# Duinopeak-Mazebot-v0_1.net
KiCad netlist of a schematic drawn in EAGLE
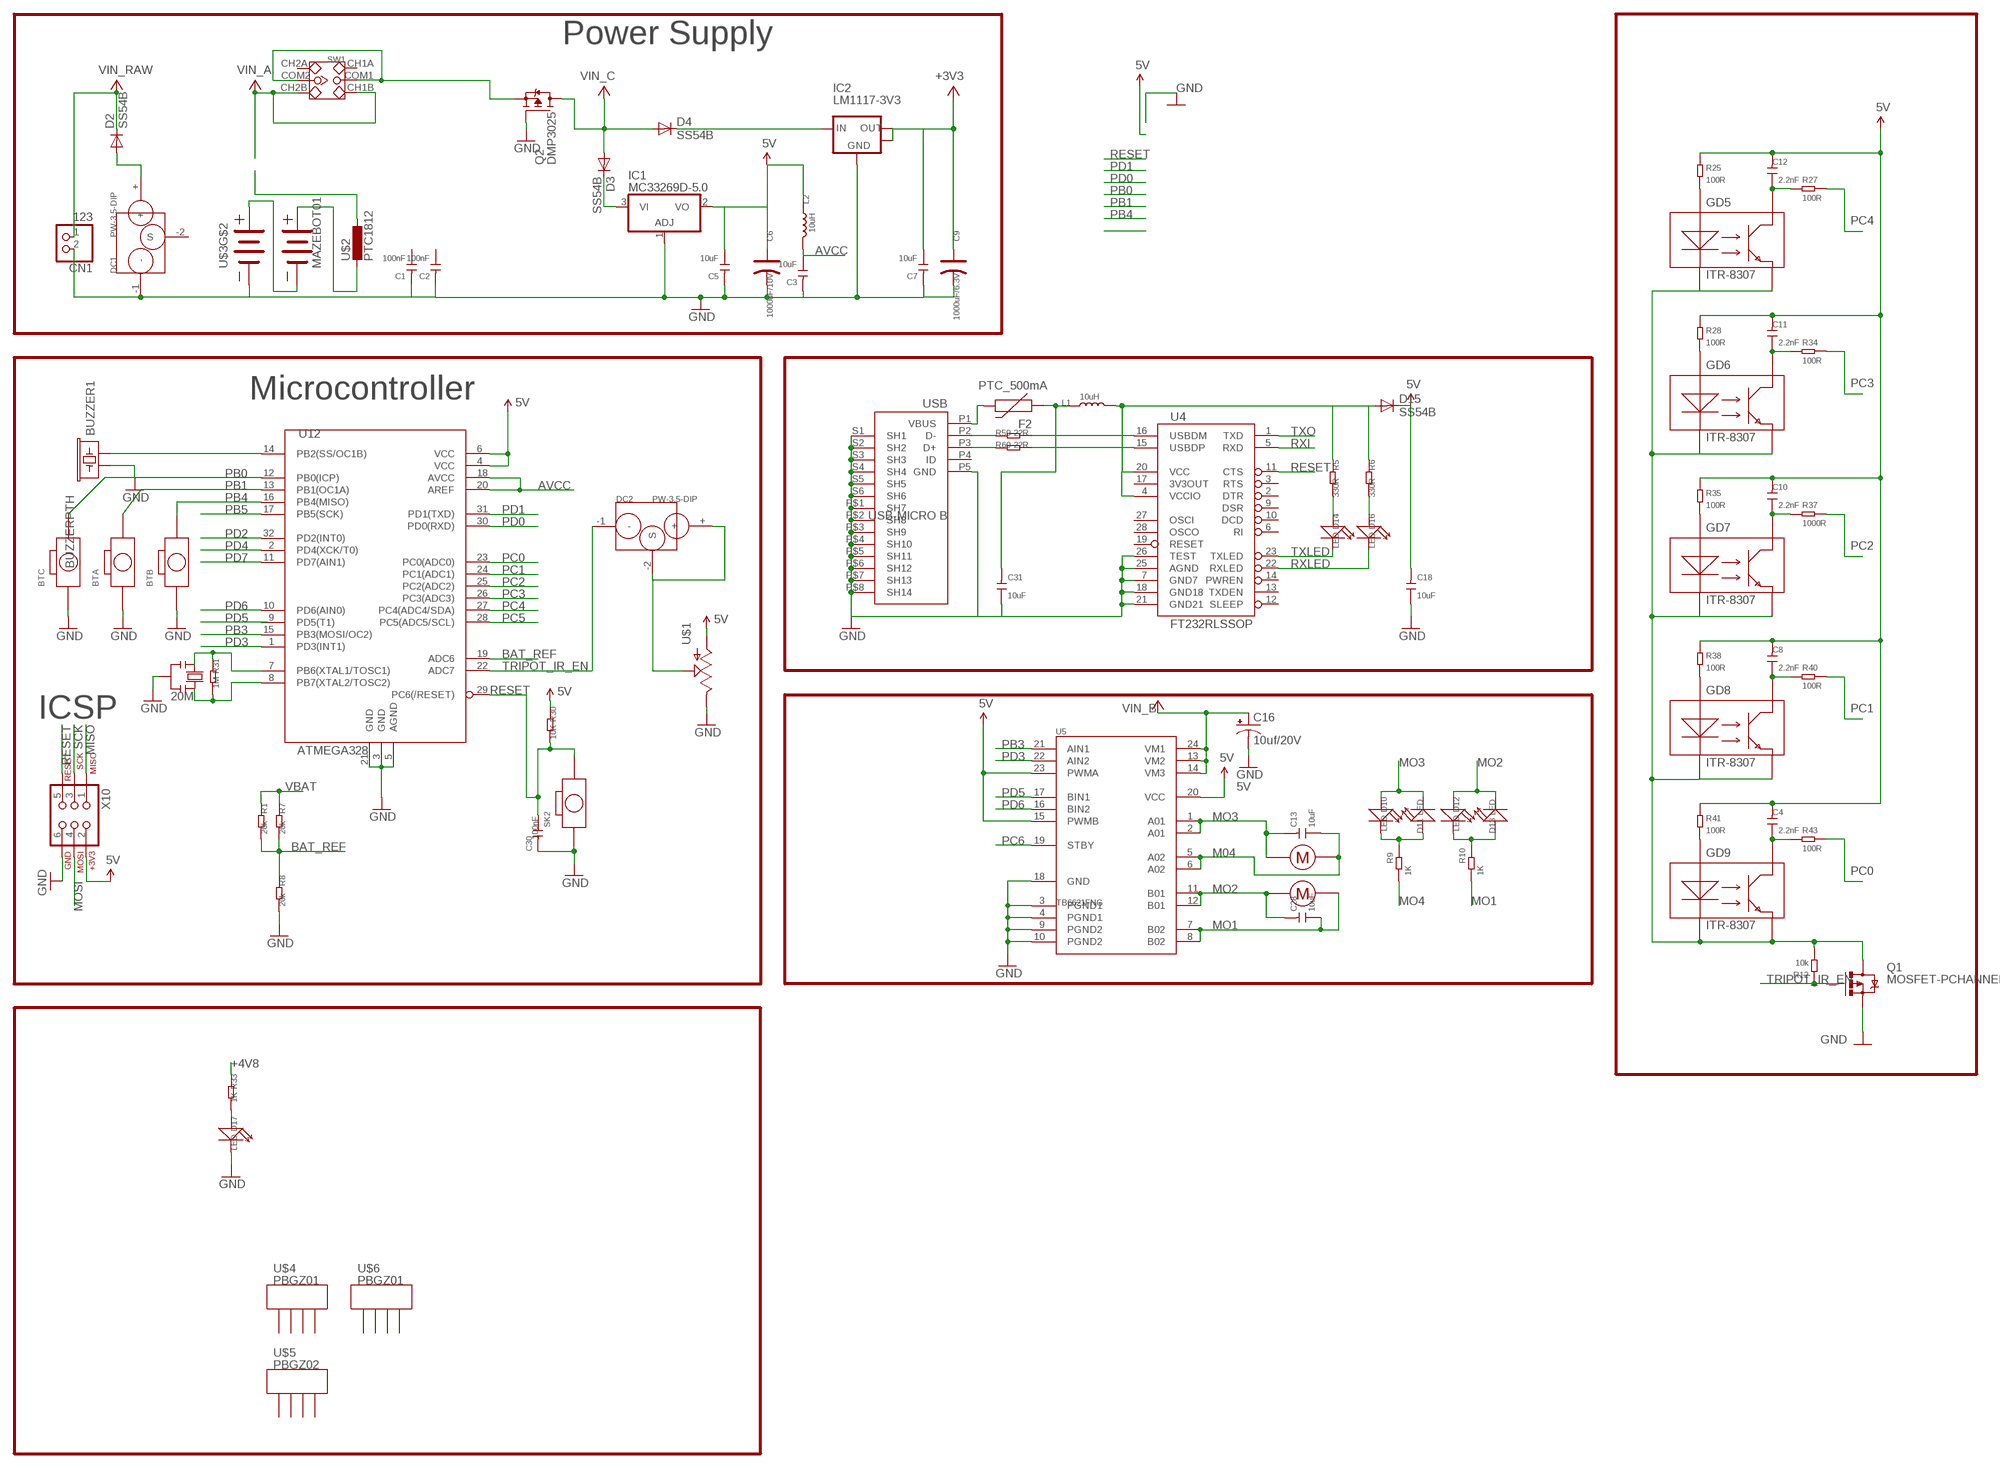
[diagram p0: schematic, sheet 1]

(export (version "E")
  (design (tool "Eeschema 10.0.6"))
  (components
    (comp (ref "BTA")
      (value "BOTTON-2P-90")
      (footprint "eagle-import:2P-7.62X3.56-90D")
      (libsource (lib "eagle-import") (part "BOTTON-2P-90"))
    )
    (comp (ref "BTB")
      (value "BOTTON-2P-90")
      (footprint "eagle-import:2P-7.62X3.56-90D")
      (libsource (lib "eagle-import") (part "BOTTON-2P-90"))
    )
    (comp (ref "BTC")
      (value "BOTTON-2P-90")
      (footprint "eagle-import:2P-7.62X3.56-90D")
      (libsource (lib "eagle-import") (part "BOTTON-2P-90"))
    )
    (comp (ref "BUZZER1")
      (value "BUZZERPTH")
      (footprint "eagle-import:BUZZER-12MM")
      (libsource (lib "eagle-import") (part "BUZZERPTH"))
    )
    (comp (ref "C1")
      (value "100nF")
      (footprint "eagle-import:C0603")
      (libsource (lib "eagle-import") (part "C-0603"))
    )
    (comp (ref "C2")
      (value "100nF")
      (footprint "eagle-import:C0603")
      (libsource (lib "eagle-import") (part "C-0603"))
    )
    (comp (ref "C3")
      (value "10uF")
      (footprint "eagle-import:C0805")
      (libsource (lib "eagle-import") (part "C-0805"))
    )
    (comp (ref "C4")
      (value "2.2nF")
      (footprint "eagle-import:C0603")
      (libsource (lib "eagle-import") (part "C-0603"))
    )
    (comp (ref "C5")
      (value "10uF")
      (footprint "eagle-import:C0805")
      (libsource (lib "eagle-import") (part "C-0805"))
    )
    (comp (ref "C6")
      (value "1000uF/10V")
      (footprint "eagle-import:ELECTRO-8.2MM")
      (libsource (lib "eagle-import") (part "CAP-D8.2/3.05"))
    )
    (comp (ref "C7")
      (value "10uF")
      (footprint "eagle-import:C0805")
      (libsource (lib "eagle-import") (part "C-0805"))
    )
    (comp (ref "C8")
      (value "2.2nF")
      (footprint "eagle-import:C0603")
      (libsource (lib "eagle-import") (part "C-0603"))
    )
    (comp (ref "C9")
      (value "1000uF/6.3V")
      (footprint "eagle-import:ELECTRO-8.2MM")
      (libsource (lib "eagle-import") (part "CAP-D8.2/3.05"))
    )
    (comp (ref "C10")
      (value "2.2nF")
      (footprint "eagle-import:C0603")
      (libsource (lib "eagle-import") (part "C-0603"))
    )
    (comp (ref "C11")
      (value "2.2nF")
      (footprint "eagle-import:C0603")
      (libsource (lib "eagle-import") (part "C-0603"))
    )
    (comp (ref "C12")
      (value "2.2nF")
      (footprint "eagle-import:C0603")
      (libsource (lib "eagle-import") (part "C-0603"))
    )
    (comp (ref "C13")
      (value "10uF")
      (footprint "eagle-import:C0805")
      (libsource (lib "eagle-import") (part "C-0805"))
    )
    (comp (ref "C16")
      (value "10uf/20V")
      (footprint "eagle-import:EIA3216")
      (libsource (lib "eagle-import") (part "CAP_POL1206"))
    )
    (comp (ref "C18")
      (value "10uF")
      (footprint "eagle-import:C0603")
      (libsource (lib "eagle-import") (part "C-0603"))
    )
    (comp (ref "C28")
      (value "10uF")
      (footprint "eagle-import:C0805")
      (libsource (lib "eagle-import") (part "C-0805"))
    )
    (comp (ref "C30")
      (value "100nF")
      (footprint "eagle-import:C0603")
      (libsource (lib "eagle-import") (part "C-0603"))
    )
    (comp (ref "C31")
      (value "10uF")
      (footprint "eagle-import:C0805")
      (libsource (lib "eagle-import") (part "C-0805"))
    )
    (comp (ref "CN1")
      (value "123")
      (footprint "eagle-import:JST-PH-2-SMT-RA")
      (libsource (lib "eagle-import") (part "JST_2PIN-SMT-RA"))
    )
    (comp (ref "D2")
      (value "SS54B")
      (footprint "eagle-import:SMB")
      (libsource (lib "eagle-import") (part "DIODE-SMB"))
    )
    (comp (ref "D3")
      (value "SS54B")
      (footprint "eagle-import:SMB")
      (libsource (lib "eagle-import") (part "DIODE-SMB"))
    )
    (comp (ref "D4")
      (value "SS54B")
      (footprint "eagle-import:SMB")
      (libsource (lib "eagle-import") (part "DIODE-SMB"))
    )
    (comp (ref "D10")
      (value "LED")
      (footprint "eagle-import:LED-0603")
      (libsource (lib "eagle-import") (part "LED'0603'"))
    )
    (comp (ref "D11")
      (value "LED")
      (footprint "eagle-import:LED-0603")
      (libsource (lib "eagle-import") (part "LED'0603'"))
    )
    (comp (ref "D12")
      (value "LED")
      (footprint "eagle-import:LED-0603")
      (libsource (lib "eagle-import") (part "LED'0603'"))
    )
    (comp (ref "D13")
      (value "LED")
      (footprint "eagle-import:LED-0603")
      (libsource (lib "eagle-import") (part "LED'0603'"))
    )
    (comp (ref "D14")
      (value "LED")
      (footprint "eagle-import:LED-0603")
      (libsource (lib "eagle-import") (part "LED'0603'"))
    )
    (comp (ref "D15")
      (value "SS54B")
      (footprint "eagle-import:SMB")
      (libsource (lib "eagle-import") (part "DIODE-SMB"))
    )
    (comp (ref "D16")
      (value "LED")
      (footprint "eagle-import:LED-0603")
      (libsource (lib "eagle-import") (part "LED'0603'"))
    )
    (comp (ref "D17")
      (value "LED")
      (footprint "eagle-import:LED-0603")
      (libsource (lib "eagle-import") (part "LED'0603'"))
    )
    (comp (ref "DC1")
      (value "PW-3.5-DIP")
      (footprint "eagle-import:PW-3.5-DIP")
      (libsource (lib "eagle-import") (part "PW-3.5-DIP"))
    )
    (comp (ref "DC2")
      (value "PW-3.5-DIP")
      (footprint "eagle-import:PW-3.5-DIP")
      (libsource (lib "eagle-import") (part "PW-3.5-DIP"))
    )
    (comp (ref "F2")
      (value "PTC_500mA")
      (footprint "eagle-import:PTC-1206")
      (libsource (lib "eagle-import") (part "PTCSMD"))
    )
    (comp (ref "GD5")
      (value "ITR-8307")
      (footprint "eagle-import:ITR-8307")
      (libsource (lib "eagle-import") (part "ITR-8307"))
    )
    (comp (ref "GD6")
      (value "ITR-8307")
      (footprint "eagle-import:ITR-8307")
      (libsource (lib "eagle-import") (part "ITR-8307"))
    )
    (comp (ref "GD7")
      (value "ITR-8307")
      (footprint "eagle-import:ITR-8307")
      (libsource (lib "eagle-import") (part "ITR-8307"))
    )
    (comp (ref "GD8")
      (value "ITR-8307")
      (footprint "eagle-import:ITR-8307")
      (libsource (lib "eagle-import") (part "ITR-8307"))
    )
    (comp (ref "GD9")
      (value "ITR-8307")
      (footprint "eagle-import:ITR-8307")
      (libsource (lib "eagle-import") (part "ITR-8307"))
    )
    (comp (ref "IC1")
      (value "MC33269D-5.0")
      (footprint "eagle-import:DPACK")
      (libsource (lib "eagle-import") (part "MC33269?D"))
    )
    (comp (ref "IC2")
      (value "LM1117-3V3")
      (footprint "eagle-import:SOT223")
      (libsource (lib "eagle-import") (part "LM1117-SOT223"))
    )
    (comp (ref "L1")
      (value "10uH")
      (footprint "eagle-import:L0805")
      (libsource (lib "eagle-import") (part "L'0805'"))
    )
    (comp (ref "L2")
      (value "10uH")
      (footprint "eagle-import:L0805")
      (libsource (lib "eagle-import") (part "L'0805'"))
    )
    (comp (ref "Q1")
      (value "MOSFET-PCHANNEL")
      (footprint "eagle-import:SOT23")
      (libsource (lib "eagle-import") (part "MOSFET-PCHANNEL"))
    )
    (comp (ref "Q2")
      (value "DMP3025")
      (footprint "eagle-import:TO252")
      (libsource (lib "eagle-import") (part "SPD30P06PTO252"))
    )
    (comp (ref "R1")
      (value "20k")
      (footprint "eagle-import:R0603")
      (libsource (lib "eagle-import") (part "R-0603"))
    )
    (comp (ref "R5")
      (value "330R")
      (footprint "eagle-import:R0603")
      (libsource (lib "eagle-import") (part "R-0603"))
    )
    (comp (ref "R6")
      (value "330R")
      (footprint "eagle-import:R0603")
      (libsource (lib "eagle-import") (part "R-0603"))
    )
    (comp (ref "R7")
      (value "20k")
      (footprint "eagle-import:R0603")
      (libsource (lib "eagle-import") (part "R-0603"))
    )
    (comp (ref "R8")
      (value "20k")
      (footprint "eagle-import:R0603")
      (libsource (lib "eagle-import") (part "R-0603"))
    )
    (comp (ref "R9")
      (value "1K")
      (footprint "eagle-import:R0603")
      (libsource (lib "eagle-import") (part "R-0603"))
    )
    (comp (ref "R10")
      (value "1K")
      (footprint "eagle-import:R0603")
      (libsource (lib "eagle-import") (part "R-0603"))
    )
    (comp (ref "R12")
      (value "10k")
      (footprint "eagle-import:R0603")
      (libsource (lib "eagle-import") (part "R-0603"))
    )
    (comp (ref "R25")
      (value "100R")
      (footprint "eagle-import:R0603")
      (libsource (lib "eagle-import") (part "R-0603"))
    )
    (comp (ref "R27")
      (value "100R")
      (footprint "eagle-import:R0603")
      (libsource (lib "eagle-import") (part "R-0603"))
    )
    (comp (ref "R28")
      (value "100R")
      (footprint "eagle-import:R0603")
      (libsource (lib "eagle-import") (part "R-0603"))
    )
    (comp (ref "R30")
      (value "10K")
      (footprint "eagle-import:R0603")
      (libsource (lib "eagle-import") (part "R-0603"))
    )
    (comp (ref "R31")
      (value "1M")
      (footprint "eagle-import:R0603")
      (libsource (lib "eagle-import") (part "R-0603"))
    )
    (comp (ref "R33")
      (value "1K")
      (footprint "eagle-import:R0603")
      (libsource (lib "eagle-import") (part "R-0603"))
    )
    (comp (ref "R34")
      (value "100R")
      (footprint "eagle-import:R0603")
      (libsource (lib "eagle-import") (part "R-0603"))
    )
    (comp (ref "R35")
      (value "100R")
      (footprint "eagle-import:R0603")
      (libsource (lib "eagle-import") (part "R-0603"))
    )
    (comp (ref "R37")
      (value "1000R")
      (footprint "eagle-import:R0603")
      (libsource (lib "eagle-import") (part "R-0603"))
    )
    (comp (ref "R38")
      (value "100R")
      (footprint "eagle-import:R0603")
      (libsource (lib "eagle-import") (part "R-0603"))
    )
    (comp (ref "R40")
      (value "100R")
      (footprint "eagle-import:R0603")
      (libsource (lib "eagle-import") (part "R-0603"))
    )
    (comp (ref "R41")
      (value "100R")
      (footprint "eagle-import:R0603")
      (libsource (lib "eagle-import") (part "R-0603"))
    )
    (comp (ref "R43")
      (value "100R")
      (footprint "eagle-import:R0603")
      (libsource (lib "eagle-import") (part "R-0603"))
    )
    (comp (ref "R59")
      (value "22R")
      (footprint "eagle-import:R0603")
      (libsource (lib "eagle-import") (part "R-0603"))
    )
    (comp (ref "R60")
      (value "22R")
      (footprint "eagle-import:R0603")
      (libsource (lib "eagle-import") (part "R-0603"))
    )
    (comp (ref "SK2")
      (value "BOTTON-2P-90")
      (footprint "eagle-import:2P-7.62X3.56-90D")
      (libsource (lib "eagle-import") (part "BOTTON-2P-90"))
    )
    (comp (ref "SW1")
      (value "SWITCH-2CH-6P'90D'")
      (footprint "eagle-import:6P-2CH-2.54-9.0X3.6-90D")
      (libsource (lib "eagle-import") (part "SWITCH-2CH-6P'90D'"))
    )
    (comp (ref "U$1")
      (value "POTTRIM")
      (footprint "eagle-import:TRIM_POT")
      (libsource (lib "eagle-import") (part "POTTRIM"))
    )
    (comp (ref "U$2")
      (value "PTC1812")
      (footprint "eagle-import:PTC-L1812")
      (libsource (lib "eagle-import") (part "PTC1812"))
    )
    (comp (ref "U$3")
      (value "MAZEBOT01")
      (footprint "eagle-import:MAZEBOT-P1")
      (libsource (lib "eagle-import") (part "MAZEBOT01"))
    )
    (comp (ref "U$4")
      (value "PBGZ01")
      (footprint "eagle-import:PBGZ-22X33MM")
      (libsource (lib "eagle-import") (part "PBGZ01"))
    )
    (comp (ref "U$5")
      (value "PBGZ02")
      (footprint "eagle-import:PBGZ-20X55MM")
      (libsource (lib "eagle-import") (part "PBGZ02"))
    )
    (comp (ref "U$6")
      (value "PBGZ01")
      (footprint "eagle-import:PBGZ-22X33MM")
      (libsource (lib "eagle-import") (part "PBGZ01"))
    )
    (comp (ref "U4")
      (value "FT232RLSSOP")
      (footprint "eagle-import:SSOP28DB")
      (libsource (lib "eagle-import") (part "FT232RLSSOP"))
    )
    (comp (ref "U5")
      (value "TB6621FNG")
      (footprint "eagle-import:SSOP24")
      (libsource (lib "eagle-import") (part "TB6621FNG"))
    )
    (comp (ref "U12")
      (value "ATMEGA328")
      (footprint "eagle-import:TQFP32-08")
      (libsource (lib "eagle-import") (part "ATMEGA168"))
    )
    (comp (ref "USB")
      (value "USB-MICRO B")
      (footprint "eagle-import:CON2_USB_MICRO_B_AT")
      (libsource (lib "eagle-import") (part "MYCON2_USB-MINI-B"))
    )
    (comp (ref "X10")
      (value "AVR_SPI_PRG_62X3_LOCK")
      (footprint "eagle-import:2X3_LOCK")
      (libsource (lib "eagle-import") (part "AVR_SPI_PRG_62X3_LOCK"))
    )
    (comp (ref "Y1")
      (value "20M")
      (footprint "eagle-import:RESONATOR")
      (libsource (lib "eagle-import") (part "RESONATORMU"))
    )
  )
  (nets
    (net (code "1") (name "+3V3") (class "Default")
      (node (ref "C7") (pin "1") (pinfunction "1_1") (pintype "passive"))
      (node (ref "C9") (pin "1") (pinfunction "+_1") (pintype "passive"))
      (node (ref "IC2") (pin "2") (pinfunction "OUT_2") (pintype "output"))
      (node (ref "IC2") (pin "4") (pinfunction "OUT_4") (pintype "output"))
    )
    (net (code "2") (name "+4V8") (class "Default")
      (node (ref "R33") (pin "1") (pinfunction "1_1") (pintype "passive"))
    )
    (net (code "3") (name "5V") (class "Default")
      (node (ref "C10") (pin "2") (pinfunction "2_2") (pintype "passive"))
      (node (ref "C11") (pin "2") (pinfunction "2_2") (pintype "passive"))
      (node (ref "C12") (pin "2") (pinfunction "2_2") (pintype "passive"))
      (node (ref "C18") (pin "2") (pinfunction "2_2") (pintype "passive"))
      (node (ref "C4") (pin "2") (pinfunction "2_2") (pintype "passive"))
      (node (ref "C5") (pin "1") (pinfunction "1_1") (pintype "passive"))
      (node (ref "C6") (pin "1") (pinfunction "+_1") (pintype "passive"))
      (node (ref "C8") (pin "2") (pinfunction "2_2") (pintype "passive"))
      (node (ref "D15") (pin "C") (pinfunction "C_C") (pintype "passive"))
      (node (ref "IC1") (pin "2") (pinfunction "VO_2") (pintype "passive"))
      (node (ref "L2") (pin "1") (pinfunction "1_1") (pintype "passive"))
      (node (ref "R25") (pin "1") (pinfunction "1_1") (pintype "passive"))
      (node (ref "R28") (pin "1") (pinfunction "1_1") (pintype "passive"))
      (node (ref "R30") (pin "1") (pinfunction "1_1") (pintype "passive"))
      (node (ref "R35") (pin "1") (pinfunction "1_1") (pintype "passive"))
      (node (ref "R38") (pin "1") (pinfunction "1_1") (pintype "passive"))
      (node (ref "R41") (pin "1") (pinfunction "1_1") (pintype "passive"))
      (node (ref "U$1") (pin "3") (pinfunction "A_3") (pintype "passive"))
      (node (ref "U12") (pin "4") (pinfunction "VCC_4") (pintype "bidirectional"))
      (node (ref "U12") (pin "6") (pinfunction "VCC_6") (pintype "bidirectional"))
      (node (ref "U5") (pin "15") (pinfunction "PWMB_15") (pintype "bidirectional"))
      (node (ref "U5") (pin "20") (pinfunction "VCC_20") (pintype "bidirectional"))
      (node (ref "U5") (pin "23") (pinfunction "PWMA_23") (pintype "bidirectional"))
      (node (ref "X10") (pin "2") (pinfunction "2_2") (pintype "passive"))
    )
    (net (code "4") (name "AVCC") (class "Default")
      (node (ref "C3") (pin "1") (pinfunction "1_1") (pintype "passive"))
      (node (ref "L2") (pin "2") (pinfunction "2_2") (pintype "passive"))
      (node (ref "U12") (pin "18") (pinfunction "AVCC_18") (pintype "bidirectional"))
      (node (ref "U12") (pin "20") (pinfunction "AREF_20") (pintype "bidirectional"))
    )
    (net (code "5") (name "BAT_REF") (class "Default")
      (node (ref "R1") (pin "2") (pinfunction "2_2") (pintype "passive"))
      (node (ref "R7") (pin "2") (pinfunction "2_2") (pintype "passive"))
      (node (ref "R8") (pin "1") (pinfunction "1_1") (pintype "passive"))
      (node (ref "U12") (pin "19") (pinfunction "ADC6_19") (pintype "bidirectional"))
    )
    (net (code "6") (name "GND") (class "Default")
      (node (ref "BTA") (pin "P$1") (pinfunction "1_P$1") (pintype "bidirectional"))
      (node (ref "BTB") (pin "P$1") (pinfunction "1_P$1") (pintype "bidirectional"))
      (node (ref "BTC") (pin "P$1") (pinfunction "1_P$1") (pintype "bidirectional"))
      (node (ref "BUZZER1") (pin "+") (pinfunction "1_+") (pintype "passive"))
      (node (ref "C1") (pin "2") (pinfunction "2_2") (pintype "passive"))
      (node (ref "C16") (pin "C") (pinfunction "-_C") (pintype "passive"))
      (node (ref "C18") (pin "1") (pinfunction "1_1") (pintype "passive"))
      (node (ref "C2") (pin "2") (pinfunction "2_2") (pintype "passive"))
      (node (ref "C3") (pin "2") (pinfunction "2_2") (pintype "passive"))
      (node (ref "C30") (pin "2") (pinfunction "2_2") (pintype "passive"))
      (node (ref "C31") (pin "1") (pinfunction "1_1") (pintype "passive"))
      (node (ref "C5") (pin "2") (pinfunction "2_2") (pintype "passive"))
      (node (ref "C6") (pin "2") (pinfunction "-_2") (pintype "passive"))
      (node (ref "C7") (pin "2") (pinfunction "2_2") (pintype "passive"))
      (node (ref "C9") (pin "2") (pinfunction "-_2") (pintype "passive"))
      (node (ref "CN1") (pin "2") (pinfunction "1_2") (pintype "passive"))
      (node (ref "D17") (pin "-") (pinfunction "-_-") (pintype "passive"))
      (node (ref "DC1") (pin "-1") (pinfunction "-_-1") (pintype "bidirectional"))
      (node (ref "IC1") (pin "1") (pinfunction "ADJ_1") (pintype "input"))
      (node (ref "IC2") (pin "1") (pinfunction "GND_1") (pintype "input"))
      (node (ref "Q1") (pin "2") (pinfunction "S_2") (pintype "passive"))
      (node (ref "Q2") (pin "1") (pinfunction "G_1") (pintype "passive"))
      (node (ref "R8") (pin "2") (pinfunction "2_2") (pintype "passive"))
      (node (ref "SK2") (pin "P$1") (pinfunction "1_P$1") (pintype "bidirectional"))
      (node (ref "U$1") (pin "2") (pinfunction "E_2") (pintype "passive"))
      (node (ref "U$3") (pin "D1") (pinfunction "D1_D1") (pintype "bidirectional"))
      (node (ref "U12") (pin "21") (pinfunction "GND_21") (pintype "bidirectional"))
      (node (ref "U12") (pin "3") (pinfunction "GND_3") (pintype "bidirectional"))
      (node (ref "U12") (pin "5") (pinfunction "AGND_5") (pintype "bidirectional"))
      (node (ref "U4") (pin "18") (pinfunction "GND18_18") (pintype "power_in"))
      (node (ref "U4") (pin "21") (pinfunction "GND21_21") (pintype "power_in"))
      (node (ref "U4") (pin "25") (pinfunction "AGND_25") (pintype "power_in"))
      (node (ref "U4") (pin "26") (pinfunction "TEST_26") (pintype "input"))
      (node (ref "U4") (pin "7") (pinfunction "GND7_7") (pintype "power_in"))
      (node (ref "U5") (pin "10") (pinfunction "PGND2_10") (pintype "bidirectional"))
      (node (ref "U5") (pin "18") (pinfunction "GND_18") (pintype "bidirectional"))
      (node (ref "U5") (pin "3") (pinfunction "PGND1_3") (pintype "bidirectional"))
      (node (ref "U5") (pin "4") (pinfunction "PGND1_4") (pintype "bidirectional"))
      (node (ref "U5") (pin "9") (pinfunction "PGND2_9") (pintype "bidirectional"))
      (node (ref "USB") (pin "P$1") (pinfunction "SH7_P$1") (pintype "passive"))
      (node (ref "USB") (pin "P$2") (pinfunction "SH8_P$2") (pintype "passive"))
      (node (ref "USB") (pin "P$3") (pinfunction "SH9_P$3") (pintype "passive"))
      (node (ref "USB") (pin "P$4") (pinfunction "SH10_P$4") (pintype "passive"))
      (node (ref "USB") (pin "P$5") (pinfunction "SH11_P$5") (pintype "passive"))
      (node (ref "USB") (pin "P$6") (pinfunction "SH12_P$6") (pintype "passive"))
      (node (ref "USB") (pin "P$7") (pinfunction "SH13_P$7") (pintype "passive"))
      (node (ref "USB") (pin "P$8") (pinfunction "SH14_P$8") (pintype "passive"))
      (node (ref "USB") (pin "P5") (pinfunction "GND_P5") (pintype "passive"))
      (node (ref "USB") (pin "S1") (pinfunction "SH1_S1") (pintype "passive"))
      (node (ref "USB") (pin "S2") (pinfunction "SH2_S2") (pintype "passive"))
      (node (ref "USB") (pin "S3") (pinfunction "SH3_S3") (pintype "passive"))
      (node (ref "USB") (pin "S4") (pinfunction "SH4_S4") (pintype "passive"))
      (node (ref "USB") (pin "S5") (pinfunction "SH5_S5") (pintype "passive"))
      (node (ref "USB") (pin "S6") (pinfunction "SH6_S6") (pintype "passive"))
      (node (ref "X10") (pin "6") (pinfunction "6_6") (pintype "passive"))
      (node (ref "Y1") (pin "2") (pinfunction "2_2") (pintype "passive"))
    )
    (net (code "7") (name "M04") (class "Default")
      (node (ref "C13") (pin "1") (pinfunction "1_1") (pintype "passive"))
      (node (ref "U$3") (pin "M2") (pinfunction "M2_M2") (pintype "bidirectional"))
      (node (ref "U5") (pin "5") (pinfunction "A02_5") (pintype "bidirectional"))
      (node (ref "U5") (pin "6") (pinfunction "A02_6") (pintype "bidirectional"))
    )
    (net (code "8") (name "MISO") (class "Default")
      (node (ref "X10") (pin "1") (pinfunction "1_1") (pintype "passive"))
    )
    (net (code "9") (name "MO1") (class "Default")
      (node (ref "C28") (pin "1") (pinfunction "1_1") (pintype "passive"))
      (node (ref "R10") (pin "2") (pinfunction "2_2") (pintype "passive"))
      (node (ref "U$3") (pin "M4") (pinfunction "M4_M4") (pintype "bidirectional"))
      (node (ref "U5") (pin "7") (pinfunction "B02_7") (pintype "bidirectional"))
      (node (ref "U5") (pin "8") (pinfunction "B02_8") (pintype "bidirectional"))
    )
    (net (code "10") (name "MO2") (class "Default")
      (node (ref "C28") (pin "2") (pinfunction "2_2") (pintype "passive"))
      (node (ref "D12") (pin "+") (pinfunction "+_+") (pintype "passive"))
      (node (ref "D13") (pin "-") (pinfunction "-_-") (pintype "passive"))
      (node (ref "U$3") (pin "M3") (pinfunction "M3_M3") (pintype "bidirectional"))
      (node (ref "U5") (pin "11") (pinfunction "B01_11") (pintype "bidirectional"))
      (node (ref "U5") (pin "12") (pinfunction "B01_12") (pintype "bidirectional"))
    )
    (net (code "11") (name "MO3") (class "Default")
      (node (ref "C13") (pin "2") (pinfunction "2_2") (pintype "passive"))
      (node (ref "D10") (pin "+") (pinfunction "+_+") (pintype "passive"))
      (node (ref "D11") (pin "-") (pinfunction "-_-") (pintype "passive"))
      (node (ref "U$3") (pin "M1") (pinfunction "M1_M1") (pintype "bidirectional"))
      (node (ref "U5") (pin "1") (pinfunction "A01_1") (pintype "bidirectional"))
      (node (ref "U5") (pin "2") (pinfunction "A01_2") (pintype "bidirectional"))
    )
    (net (code "12") (name "MO4") (class "Default")
      (node (ref "R9") (pin "2") (pinfunction "2_2") (pintype "passive"))
    )
    (net (code "13") (name "MOSI") (class "Default")
      (node (ref "X10") (pin "4") (pinfunction "4_4") (pintype "passive"))
    )
    (net (code "14") (name "Net-(BUZZER1-2)") (class "Default")
      (node (ref "BUZZER1") (pin "-") (pinfunction "2_-") (pintype "passive"))
      (node (ref "U12") (pin "14") (pinfunction "PB2(SS/OC1B)_14") (pintype "bidirectional"))
    )
    (net (code "15") (name "Net-(C4-Pad1)") (class "Default")
      (node (ref "C4") (pin "1") (pinfunction "1_1") (pintype "passive"))
      (node (ref "GD9") (pin "3") (pinfunction "3_3") (pintype "bidirectional"))
      (node (ref "R43") (pin "2") (pinfunction "2_2") (pintype "passive"))
    )
    (net (code "16") (name "Net-(C8-Pad1)") (class "Default")
      (node (ref "C8") (pin "1") (pinfunction "1_1") (pintype "passive"))
      (node (ref "GD8") (pin "3") (pinfunction "3_3") (pintype "bidirectional"))
      (node (ref "R40") (pin "2") (pinfunction "2_2") (pintype "passive"))
    )
    (net (code "17") (name "Net-(C10-Pad1)") (class "Default")
      (node (ref "C10") (pin "1") (pinfunction "1_1") (pintype "passive"))
      (node (ref "GD7") (pin "3") (pinfunction "3_3") (pintype "bidirectional"))
      (node (ref "R37") (pin "2") (pinfunction "2_2") (pintype "passive"))
    )
    (net (code "18") (name "Net-(C11-Pad1)") (class "Default")
      (node (ref "C11") (pin "1") (pinfunction "1_1") (pintype "passive"))
      (node (ref "GD6") (pin "3") (pinfunction "3_3") (pintype "bidirectional"))
      (node (ref "R34") (pin "2") (pinfunction "2_2") (pintype "passive"))
    )
    (net (code "19") (name "Net-(C12-Pad1)") (class "Default")
      (node (ref "C12") (pin "1") (pinfunction "1_1") (pintype "passive"))
      (node (ref "GD5") (pin "3") (pinfunction "3_3") (pintype "bidirectional"))
      (node (ref "R27") (pin "2") (pinfunction "2_2") (pintype "passive"))
    )
    (net (code "20") (name "Net-(C31-Pad2)") (class "Default")
      (node (ref "C31") (pin "2") (pinfunction "2_2") (pintype "passive"))
      (node (ref "F2") (pin "1") (pinfunction "1_1") (pintype "bidirectional"))
      (node (ref "L1") (pin "1") (pinfunction "1_1") (pintype "passive"))
    )
    (net (code "21") (name "Net-(D2-PadA)") (class "Default")
      (node (ref "D2") (pin "A") (pinfunction "A_A") (pintype "passive"))
      (node (ref "DC1") (pin "+") (pinfunction "+_+") (pintype "bidirectional"))
    )
    (net (code "22") (name "Net-(D10-Pad-)") (class "Default")
      (node (ref "D10") (pin "-") (pinfunction "-_-") (pintype "passive"))
      (node (ref "D11") (pin "+") (pinfunction "+_+") (pintype "passive"))
      (node (ref "R9") (pin "1") (pinfunction "1_1") (pintype "passive"))
    )
    (net (code "23") (name "Net-(D12-Pad-)") (class "Default")
      (node (ref "D12") (pin "-") (pinfunction "-_-") (pintype "passive"))
      (node (ref "D13") (pin "+") (pinfunction "+_+") (pintype "passive"))
      (node (ref "R10") (pin "1") (pinfunction "1_1") (pintype "passive"))
    )
    (net (code "24") (name "Net-(D14-Pad+)") (class "Default")
      (node (ref "D14") (pin "+") (pinfunction "+_+") (pintype "passive"))
      (node (ref "R5") (pin "2") (pinfunction "2_2") (pintype "passive"))
    )
    (net (code "25") (name "Net-(D16-Pad+)") (class "Default")
      (node (ref "D16") (pin "+") (pinfunction "+_+") (pintype "passive"))
      (node (ref "R6") (pin "2") (pinfunction "2_2") (pintype "passive"))
    )
    (net (code "26") (name "Net-(D17-Pad+)") (class "Default")
      (node (ref "D17") (pin "+") (pinfunction "+_+") (pintype "passive"))
      (node (ref "R33") (pin "2") (pinfunction "2_2") (pintype "passive"))
    )
    (net (code "27") (name "Net-(DC2-S)") (class "Default")
      (node (ref "DC2") (pin "+") (pinfunction "+_+") (pintype "bidirectional"))
      (node (ref "DC2") (pin "-2") (pinfunction "S_-2") (pintype "bidirectional"))
      (node (ref "U$1") (pin "1") (pinfunction "S_1") (pintype "passive"))
    )
    (net (code "28") (name "Net-(GD5-Pad1)") (class "Default")
      (node (ref "GD5") (pin "1") (pinfunction "1_1") (pintype "bidirectional"))
      (node (ref "R25") (pin "2") (pinfunction "2_2") (pintype "passive"))
    )
    (net (code "29") (name "Net-(GD6-Pad1)") (class "Default")
      (node (ref "GD6") (pin "1") (pinfunction "1_1") (pintype "bidirectional"))
      (node (ref "R28") (pin "2") (pinfunction "2_2") (pintype "passive"))
    )
    (net (code "30") (name "Net-(GD7-Pad1)") (class "Default")
      (node (ref "GD7") (pin "1") (pinfunction "1_1") (pintype "bidirectional"))
      (node (ref "R35") (pin "2") (pinfunction "2_2") (pintype "passive"))
    )
    (net (code "31") (name "Net-(GD8-Pad1)") (class "Default")
      (node (ref "GD8") (pin "1") (pinfunction "1_1") (pintype "bidirectional"))
      (node (ref "R38") (pin "2") (pinfunction "2_2") (pintype "passive"))
    )
    (net (code "32") (name "Net-(GD9-Pad1)") (class "Default")
      (node (ref "GD9") (pin "1") (pinfunction "1_1") (pintype "bidirectional"))
      (node (ref "R41") (pin "2") (pinfunction "2_2") (pintype "passive"))
    )
    (net (code "33") (name "Net-(IC1-VI)") (class "Default")
      (node (ref "D3") (pin "C") (pinfunction "C_C") (pintype "passive"))
      (node (ref "IC1") (pin "3") (pinfunction "VI_3") (pintype "input"))
    )
    (net (code "34") (name "Net-(IC2-IN)") (class "Default")
      (node (ref "D4") (pin "C") (pinfunction "C_C") (pintype "passive"))
      (node (ref "IC2") (pin "3") (pinfunction "IN_3") (pintype "input"))
    )
    (net (code "35") (name "Net-(Q1-D)") (class "Default")
      (node (ref "GD5") (pin "2") (pinfunction "2_2") (pintype "bidirectional"))
      (node (ref "GD5") (pin "4") (pinfunction "4_4") (pintype "bidirectional"))
      (node (ref "GD6") (pin "2") (pinfunction "2_2") (pintype "bidirectional"))
      (node (ref "GD6") (pin "4") (pinfunction "4_4") (pintype "bidirectional"))
      (node (ref "GD7") (pin "2") (pinfunction "2_2") (pintype "bidirectional"))
      (node (ref "GD7") (pin "4") (pinfunction "4_4") (pintype "bidirectional"))
      (node (ref "GD8") (pin "2") (pinfunction "2_2") (pintype "bidirectional"))
      (node (ref "GD8") (pin "4") (pinfunction "4_4") (pintype "bidirectional"))
      (node (ref "GD9") (pin "2") (pinfunction "2_2") (pintype "bidirectional"))
      (node (ref "GD9") (pin "4") (pinfunction "4_4") (pintype "bidirectional"))
      (node (ref "Q1") (pin "3") (pinfunction "D_3") (pintype "passive"))
      (node (ref "R12") (pin "2") (pinfunction "2_2") (pintype "passive"))
    )
    (net (code "36") (name "Net-(Q2-S)") (class "Default")
      (node (ref "Q2") (pin "2") (pinfunction "S_2") (pintype "passive"))
      (node (ref "SW1") (pin "COM1") (pinfunction "COM1_COM1") (pintype "bidirectional"))
      (node (ref "SW1") (pin "COM2") (pinfunction "COM2_COM2") (pintype "bidirectional"))
    )
    (net (code "37") (name "Net-(U$2-Pad1)") (class "Default")
      (node (ref "U$2") (pin "1") (pinfunction "1_1") (pintype "passive"))
      (node (ref "U$3") (pin "D4") (pinfunction "D4_D4") (pintype "bidirectional"))
    )
    (net (code "38") (name "Net-(U$3-PadD2)") (class "Default")
      (node (ref "U$3") (pin "D2") (pinfunction "D2_D2") (pintype "bidirectional"))
      (node (ref "U$3") (pin "D3") (pinfunction "D3_D3") (pintype "bidirectional"))
    )
    (net (code "39") (name "Net-(U4-USBDM)") (class "Default")
      (node (ref "R59") (pin "2") (pinfunction "2_2") (pintype "passive"))
      (node (ref "U4") (pin "16") (pinfunction "USBDM_16") (pintype "bidirectional"))
    )
    (net (code "40") (name "Net-(U4-USBDP)") (class "Default")
      (node (ref "R60") (pin "2") (pinfunction "2_2") (pintype "passive"))
      (node (ref "U4") (pin "15") (pinfunction "USBDP_15") (pintype "bidirectional"))
    )
    (net (code "41") (name "Net-(U4-VCC)") (class "Default")
      (node (ref "D15") (pin "A") (pinfunction "A_A") (pintype "passive"))
      (node (ref "L1") (pin "2") (pinfunction "2_2") (pintype "passive"))
      (node (ref "R5") (pin "1") (pinfunction "1_1") (pintype "passive"))
      (node (ref "R6") (pin "1") (pinfunction "1_1") (pintype "passive"))
      (node (ref "U4") (pin "20") (pinfunction "VCC_20") (pintype "power_in"))
      (node (ref "U4") (pin "4") (pinfunction "VCCIO_4") (pintype "power_in"))
    )
    (net (code "42") (name "Net-(U12-PB6(XTAL1{slash}TOSC1))") (class "Default")
      (node (ref "R31") (pin "1") (pinfunction "1_1") (pintype "passive"))
      (node (ref "U12") (pin "7") (pinfunction "PB6(XTAL1/TOSC1)_7") (pintype "bidirectional"))
      (node (ref "Y1") (pin "1") (pinfunction "1_1") (pintype "passive"))
    )
    (net (code "43") (name "Net-(U12-PB7(XTAL2{slash}TOSC2))") (class "Default")
      (node (ref "R31") (pin "2") (pinfunction "2_2") (pintype "passive"))
      (node (ref "U12") (pin "8") (pinfunction "PB7(XTAL2/TOSC2)_8") (pintype "bidirectional"))
      (node (ref "Y1") (pin "3") (pinfunction "3_3") (pintype "passive"))
    )
    (net (code "44") (name "Net-(USB-D+)") (class "Default")
      (node (ref "R60") (pin "1") (pinfunction "1_1") (pintype "passive"))
      (node (ref "USB") (pin "P3") (pinfunction "D+_P3") (pintype "bidirectional"))
    )
    (net (code "45") (name "Net-(USB-D-)") (class "Default")
      (node (ref "R59") (pin "1") (pinfunction "1_1") (pintype "passive"))
      (node (ref "USB") (pin "P2") (pinfunction "D-_P2") (pintype "bidirectional"))
    )
    (net (code "46") (name "Net-(USB-VBUS)") (class "Default")
      (node (ref "F2") (pin "2") (pinfunction "2_2") (pintype "bidirectional"))
      (node (ref "USB") (pin "P1") (pinfunction "VBUS_P1") (pintype "power_in"))
    )
    (net (code "47") (name "PB0") (class "Default")
      (node (ref "BTC") (pin "P$2") (pinfunction "2_P$2") (pintype "bidirectional"))
      (node (ref "U12") (pin "12") (pinfunction "PB0(ICP)_12") (pintype "bidirectional"))
    )
    (net (code "48") (name "PB1") (class "Default")
      (node (ref "BTA") (pin "P$2") (pinfunction "2_P$2") (pintype "bidirectional"))
      (node (ref "U12") (pin "13") (pinfunction "PB1(OC1A)_13") (pintype "bidirectional"))
    )
    (net (code "49") (name "PB3") (class "Default")
      (node (ref "U12") (pin "15") (pinfunction "PB3(MOSI/OC2)_15") (pintype "bidirectional"))
      (node (ref "U5") (pin "21") (pinfunction "AIN1_21") (pintype "bidirectional"))
    )
    (net (code "50") (name "PB4") (class "Default")
      (node (ref "BTB") (pin "P$2") (pinfunction "2_P$2") (pintype "bidirectional"))
      (node (ref "U12") (pin "16") (pinfunction "PB4(MISO)_16") (pintype "bidirectional"))
    )
    (net (code "51") (name "PB5") (class "Default")
      (node (ref "U12") (pin "17") (pinfunction "PB5(SCK)_17") (pintype "bidirectional"))
    )
    (net (code "52") (name "PC0") (class "Default")
      (node (ref "R43") (pin "1") (pinfunction "1_1") (pintype "passive"))
      (node (ref "U12") (pin "23") (pinfunction "PC0(ADC0)_23") (pintype "bidirectional"))
    )
    (net (code "53") (name "PC1") (class "Default")
      (node (ref "R40") (pin "1") (pinfunction "1_1") (pintype "passive"))
      (node (ref "U12") (pin "24") (pinfunction "PC1(ADC1)_24") (pintype "bidirectional"))
    )
    (net (code "54") (name "PC2") (class "Default")
      (node (ref "R37") (pin "1") (pinfunction "1_1") (pintype "passive"))
      (node (ref "U12") (pin "25") (pinfunction "PC2(ADC2)_25") (pintype "bidirectional"))
    )
    (net (code "55") (name "PC3") (class "Default")
      (node (ref "R34") (pin "1") (pinfunction "1_1") (pintype "passive"))
      (node (ref "U12") (pin "26") (pinfunction "PC3(ADC3)_26") (pintype "bidirectional"))
    )
    (net (code "56") (name "PC4") (class "Default")
      (node (ref "R27") (pin "1") (pinfunction "1_1") (pintype "passive"))
      (node (ref "U12") (pin "27") (pinfunction "PC4(ADC4/SDA)_27") (pintype "bidirectional"))
    )
    (net (code "57") (name "PC5") (class "Default")
      (node (ref "U12") (pin "28") (pinfunction "PC5(ADC5/SCL)_28") (pintype "bidirectional"))
    )
    (net (code "58") (name "PC6") (class "Default")
      (node (ref "U5") (pin "19") (pinfunction "STBY_19") (pintype "bidirectional"))
    )
    (net (code "59") (name "PD0") (class "Default")
      (node (ref "U12") (pin "30") (pinfunction "PD0(RXD)_30") (pintype "bidirectional"))
    )
    (net (code "60") (name "PD1") (class "Default")
      (node (ref "U12") (pin "31") (pinfunction "PD1(TXD)_31") (pintype "bidirectional"))
    )
    (net (code "61") (name "PD2") (class "Default")
      (node (ref "U12") (pin "32") (pinfunction "PD2(INT0)_32") (pintype "bidirectional"))
    )
    (net (code "62") (name "PD3") (class "Default")
      (node (ref "U12") (pin "1") (pinfunction "PD3(INT1)_1") (pintype "bidirectional"))
      (node (ref "U5") (pin "22") (pinfunction "AIN2_22") (pintype "bidirectional"))
    )
    (net (code "63") (name "PD4") (class "Default")
      (node (ref "U12") (pin "2") (pinfunction "PD4(XCK/T0)_2") (pintype "bidirectional"))
    )
    (net (code "64") (name "PD5") (class "Default")
      (node (ref "U5") (pin "17") (pinfunction "BIN1_17") (pintype "bidirectional"))
    )
    (net (code "65") (name "PD6") (class "Default")
      (node (ref "U12") (pin "10") (pinfunction "PD6(AIN0)_10") (pintype "bidirectional"))
      (node (ref "U5") (pin "16") (pinfunction "BIN2_16") (pintype "bidirectional"))
    )
    (net (code "66") (name "PD7") (class "Default")
      (node (ref "U12") (pin "11") (pinfunction "PD7(AIN1)_11") (pintype "bidirectional"))
    )
    (net (code "67") (name "RESET") (class "Default")
      (node (ref "C30") (pin "1") (pinfunction "1_1") (pintype "passive"))
      (node (ref "R30") (pin "2") (pinfunction "2_2") (pintype "passive"))
      (node (ref "SK2") (pin "P$2") (pinfunction "2_P$2") (pintype "bidirectional"))
      (node (ref "U12") (pin "29") (pinfunction "PC6(/RESET)_29") (pintype "bidirectional"))
      (node (ref "U4") (pin "11") (pinfunction "CTS_11") (pintype "input"))
      (node (ref "X10") (pin "5") (pinfunction "5_5") (pintype "passive"))
    )
    (net (code "68") (name "RXI") (class "Default")
      (node (ref "U4") (pin "5") (pinfunction "RXD_5") (pintype "input"))
    )
    (net (code "69") (name "RXLED") (class "Default")
      (node (ref "D16") (pin "-") (pinfunction "-_-") (pintype "passive"))
      (node (ref "U4") (pin "22") (pinfunction "RXLED_22") (pintype "input"))
    )
    (net (code "70") (name "SCK") (class "Default")
      (node (ref "X10") (pin "3") (pinfunction "3_3") (pintype "passive"))
    )
    (net (code "71") (name "TRIPOT_IR_EN") (class "Default")
      (node (ref "DC2") (pin "-1") (pinfunction "-_-1") (pintype "bidirectional"))
      (node (ref "Q1") (pin "1") (pinfunction "G_1") (pintype "passive"))
      (node (ref "R12") (pin "1") (pinfunction "1_1") (pintype "passive"))
      (node (ref "U12") (pin "22") (pinfunction "ADC7_22") (pintype "bidirectional"))
    )
    (net (code "72") (name "TXLED") (class "Default")
      (node (ref "D14") (pin "-") (pinfunction "-_-") (pintype "passive"))
      (node (ref "U4") (pin "23") (pinfunction "TXLED_23") (pintype "input"))
    )
    (net (code "73") (name "TXO") (class "Default")
      (node (ref "U4") (pin "1") (pinfunction "TXD_1") (pintype "output"))
    )
    (net (code "74") (name "VBAT") (class "Default")
      (node (ref "R1") (pin "1") (pinfunction "1_1") (pintype "passive"))
      (node (ref "R7") (pin "1") (pinfunction "1_1") (pintype "passive"))
    )
    (net (code "75") (name "VIN_A") (class "Default")
      (node (ref "SW1") (pin "CH1B") (pinfunction "CH1B_CH1B") (pintype "bidirectional"))
      (node (ref "SW1") (pin "CH2B") (pinfunction "CH2B_CH2B") (pintype "bidirectional"))
    )
    (net (code "76") (name "VIN_C") (class "Default")
      (node (ref "C16") (pin "A") (pinfunction "+_A") (pintype "passive"))
      (node (ref "D3") (pin "A") (pinfunction "A_A") (pintype "passive"))
      (node (ref "D4") (pin "A") (pinfunction "A_A") (pintype "passive"))
      (node (ref "Q2") (pin "3") (pinfunction "D_3") (pintype "passive"))
      (node (ref "U5") (pin "13") (pinfunction "VM2_13") (pintype "bidirectional"))
      (node (ref "U5") (pin "14") (pinfunction "VM3_14") (pintype "bidirectional"))
      (node (ref "U5") (pin "24") (pinfunction "VM1_24") (pintype "bidirectional"))
    )
    (net (code "77") (name "VIN_RAW") (class "Default")
      (node (ref "CN1") (pin "1") (pinfunction "2_1") (pintype "passive"))
      (node (ref "D2") (pin "C") (pinfunction "C_C") (pintype "passive"))
    )
    (net (code "78") (name "unconnected-(C1-Pad1)") (class "Default")
      (node (ref "C1") (pin "1") (pinfunction "1_1") (pintype "passive"))
    )
    (net (code "79") (name "unconnected-(C2-Pad1)") (class "Default")
      (node (ref "C2") (pin "1") (pinfunction "1_1") (pintype "passive"))
    )
    (net (code "80") (name "unconnected-(DC1-S-Pad-2)") (class "Default")
      (node (ref "DC1") (pin "-2") (pinfunction "S_-2") (pintype "bidirectional"))
    )
    (net (code "81") (name "unconnected-(SW1-PadCH1A)") (class "Default")
      (node (ref "SW1") (pin "CH1A") (pinfunction "CH1A_CH1A") (pintype "bidirectional"))
    )
    (net (code "82") (name "unconnected-(SW1-PadCH2A)") (class "Default")
      (node (ref "SW1") (pin "CH2A") (pinfunction "CH2A_CH2A") (pintype "bidirectional"))
    )
    (net (code "83") (name "unconnected-(U$2-Pad2)") (class "Default")
      (node (ref "U$2") (pin "2") (pinfunction "2_2") (pintype "passive"))
    )
    (net (code "84") (name "unconnected-(U$4-Pad1)") (class "Default")
      (node (ref "U$4") (pin "1") (pinfunction "1_1") (pintype "bidirectional"))
    )
    (net (code "85") (name "unconnected-(U$4-Pad2)") (class "Default")
      (node (ref "U$4") (pin "2") (pinfunction "2_2") (pintype "bidirectional"))
    )
    (net (code "86") (name "unconnected-(U$4-Pad3)") (class "Default")
      (node (ref "U$4") (pin "3") (pinfunction "3_3") (pintype "bidirectional"))
    )
    (net (code "87") (name "unconnected-(U$4-Pad4)") (class "Default")
      (node (ref "U$4") (pin "4") (pinfunction "4_4") (pintype "bidirectional"))
    )
    (net (code "88") (name "unconnected-(U$5-Pad1)") (class "Default")
      (node (ref "U$5") (pin "1") (pinfunction "1_1") (pintype "bidirectional"))
    )
    (net (code "89") (name "unconnected-(U$5-Pad2)") (class "Default")
      (node (ref "U$5") (pin "2") (pinfunction "2_2") (pintype "bidirectional"))
    )
    (net (code "90") (name "unconnected-(U$5-Pad3)") (class "Default")
      (node (ref "U$5") (pin "3") (pinfunction "3_3") (pintype "bidirectional"))
    )
    (net (code "91") (name "unconnected-(U$5-Pad4)") (class "Default")
      (node (ref "U$5") (pin "4") (pinfunction "4_4") (pintype "bidirectional"))
    )
    (net (code "92") (name "unconnected-(U$6-Pad1)") (class "Default")
      (node (ref "U$6") (pin "1") (pinfunction "1_1") (pintype "bidirectional"))
    )
    (net (code "93") (name "unconnected-(U$6-Pad2)") (class "Default")
      (node (ref "U$6") (pin "2") (pinfunction "2_2") (pintype "bidirectional"))
    )
    (net (code "94") (name "unconnected-(U$6-Pad3)") (class "Default")
      (node (ref "U$6") (pin "3") (pinfunction "3_3") (pintype "bidirectional"))
    )
    (net (code "95") (name "unconnected-(U$6-Pad4)") (class "Default")
      (node (ref "U$6") (pin "4") (pinfunction "4_4") (pintype "bidirectional"))
    )
    (net (code "96") (name "unconnected-(U4-3V3OUT-Pad17)") (class "Default")
      (node (ref "U4") (pin "17") (pinfunction "3V3OUT_17") (pintype "output"))
    )
    (net (code "97") (name "unconnected-(U4-DCD-Pad10)") (class "Default")
      (node (ref "U4") (pin "10") (pinfunction "DCD_10") (pintype "input"))
    )
    (net (code "98") (name "unconnected-(U4-DSR-Pad9)") (class "Default")
      (node (ref "U4") (pin "9") (pinfunction "DSR_9") (pintype "input"))
    )
    (net (code "99") (name "unconnected-(U4-DTR-Pad2)") (class "Default")
      (node (ref "U4") (pin "2") (pinfunction "DTR_2") (pintype "output"))
    )
    (net (code "100") (name "unconnected-(U4-OSCI-Pad27)") (class "Default")
      (node (ref "U4") (pin "27") (pinfunction "OSCI_27") (pintype "input"))
    )
    (net (code "101") (name "unconnected-(U4-OSCO-Pad28)") (class "Default")
      (node (ref "U4") (pin "28") (pinfunction "OSCO_28") (pintype "output"))
    )
    (net (code "102") (name "unconnected-(U4-PWREN-Pad14)") (class "Default")
      (node (ref "U4") (pin "14") (pinfunction "PWREN_14") (pintype "input"))
    )
    (net (code "103") (name "unconnected-(U4-RESET-Pad19)") (class "Default")
      (node (ref "U4") (pin "19") (pinfunction "RESET_19") (pintype "input"))
    )
    (net (code "104") (name "unconnected-(U4-RI-Pad6)") (class "Default")
      (node (ref "U4") (pin "6") (pinfunction "RI_6") (pintype "input"))
    )
    (net (code "105") (name "unconnected-(U4-RTS-Pad3)") (class "Default")
      (node (ref "U4") (pin "3") (pinfunction "RTS_3") (pintype "output"))
    )
    (net (code "106") (name "unconnected-(U4-SLEEP-Pad12)") (class "Default")
      (node (ref "U4") (pin "12") (pinfunction "SLEEP_12") (pintype "input"))
    )
    (net (code "107") (name "unconnected-(U4-TXDEN-Pad13)") (class "Default")
      (node (ref "U4") (pin "13") (pinfunction "TXDEN_13") (pintype "input"))
    )
    (net (code "108") (name "unconnected-(U12-PD5(T1)-Pad9)") (class "Default")
      (node (ref "U12") (pin "9") (pinfunction "PD5(T1)_9") (pintype "bidirectional"))
    )
    (net (code "109") (name "unconnected-(USB-ID-PadP4)") (class "Default")
      (node (ref "USB") (pin "P4") (pinfunction "ID_P4") (pintype "bidirectional"))
    )
  )
)
